# SH1_-_CAN.net
KiCad netlist of a schematic drawn in Altium Designer
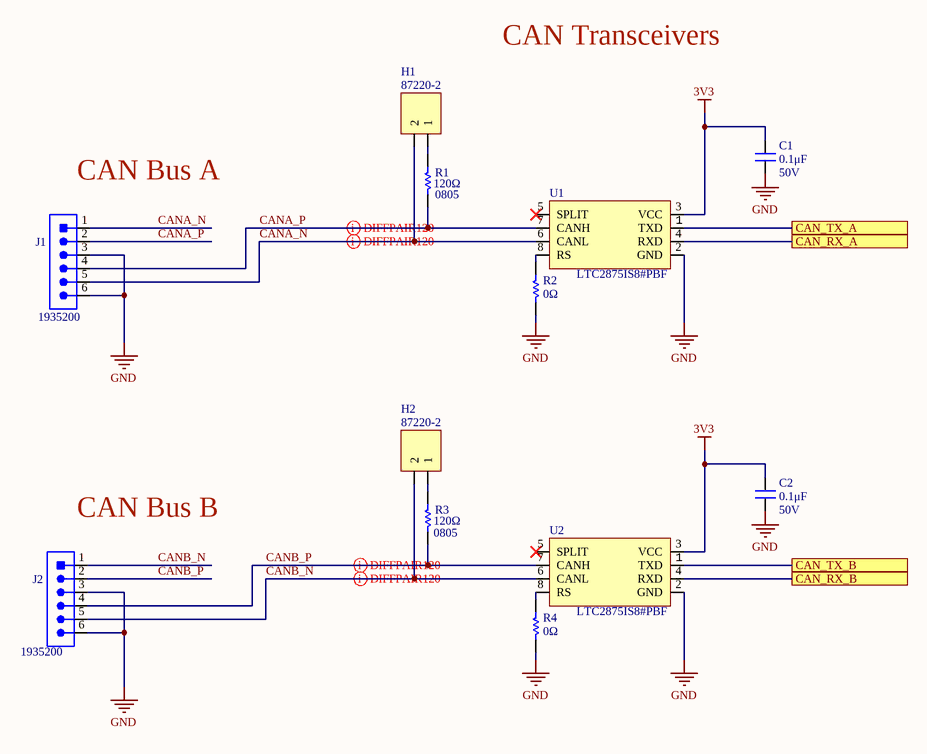
[diagram p0: SH1 - CAN.SchDoc]

(export (version "E")
  (design (tool "Eeschema 10.0.6"))
  (components
    (comp (ref "C1")
      (value "0.1μF")
      (footprint "CAP2012")
      (description "CAP CER 0.1UF 50V X7R 0805")
      (fields
        (field (name "VOLTAGE RATING") "50V")
        (field (name "LCSC PART #") "C49678")
        (field (name "Comment") "CAP_0.1uF_50V_0805")
      )
      (libsource (lib "UWRT_Schematic_Library_2020") (part "CAP_0.1uF_50V_0805"))
    )
    (comp (ref "C2")
      (value "0.1μF")
      (footprint "CAP2012")
      (description "CAP CER 0.1UF 50V X7R 0805")
      (fields
        (field (name "VOLTAGE RATING") "50V")
        (field (name "LCSC PART #") "C49678")
        (field (name "Comment") "CAP_0.1uF_50V_0805")
      )
      (libsource (lib "UWRT_Schematic_Library_2020") (part "CAP_0.1uF_50V_0805"))
    )
    (comp (ref "H1")
      (value "JUMPER")
      (footprint "HDR1X2")
      (description "HEADER 2X1")
      (fields (field (name "MANUFACTURER PART NUMBER 1") "87220-2"))
      (libsource (lib "UWRT_Schematic_Library_2020") (part "JUMPER"))
    )
    (comp (ref "H2")
      (value "JUMPER")
      (footprint "HDR1X2")
      (description "HEADER 2X1")
      (fields (field (name "MANUFACTURER PART NUMBER 1") "87220-2"))
      (libsource (lib "UWRT_Schematic_Library_2020") (part "JUMPER"))
    )
    (comp (ref "J1")
      (value "CON_6POS_SCREW_TERM")
      (footprint "1935200")
      (description "TERM BLK 6POS SIDE ENTRY 5MM")
      (fields (field (name "MANUFACTURER PART NUMBER 1") "1935200"))
      (libsource (lib "UWRT_Schematic_Library_2020") (part "CON_6POS_SCREW_TERM"))
    )
    (comp (ref "J2")
      (value "CON_6POS_SCREW_TERM")
      (footprint "1935200")
      (description "TERM BLK 6POS SIDE ENTRY 5MM")
      (fields (field (name "MANUFACTURER PART NUMBER 1") "1935200"))
      (libsource (lib "UWRT_Schematic_Library_2020") (part "CON_6POS_SCREW_TERM"))
    )
    (comp (ref "R1")
      (value "120Ω")
      (footprint "RESC0805")
      (description "RES 120 OHM 1% 1/8W 0805")
      (fields
        (field (name "LCSC PART #") "C17437")
        (field (name "PACKAGE/FOOTPRINT") "0805")
        (field (name "Comment") "RES_120Ω_0805_1%")
      )
      (libsource (lib "UWRT_Schematic_Library_2020") (part "RES_120Ω_0805_1%"))
    )
    (comp (ref "R2")
      (value "0Ω")
      (footprint "RESC0805")
      (description "RES 0 OHM JUMPER 1/8W 0805")
      (fields (field (name "LCSC PART #") "C17477") (field (name "Comment") "RES_0Ω_0805"))
      (libsource (lib "UWRT_Schematic_Library_2020") (part "RES_0Ω_0805"))
    )
    (comp (ref "R3")
      (value "120Ω")
      (footprint "RESC0805")
      (description "RES 120 OHM 1% 1/8W 0805")
      (fields
        (field (name "LCSC PART #") "C17437")
        (field (name "PACKAGE/FOOTPRINT") "0805")
        (field (name "Comment") "RES_120Ω_0805_1%")
      )
      (libsource (lib "UWRT_Schematic_Library_2020") (part "RES_120Ω_0805_1%"))
    )
    (comp (ref "R4")
      (value "0Ω")
      (footprint "RESC0805")
      (description "RES 0 OHM JUMPER 1/8W 0805")
      (fields (field (name "LCSC PART #") "C17477") (field (name "Comment") "RES_0Ω_0805"))
      (libsource (lib "UWRT_Schematic_Library_2020") (part "RES_0Ω_0805"))
    )
    (comp (ref "U1")
      (value "IC_CAN_TRANSCEIVER")
      (footprint "LT-S8_N")
      (description "IC TXRX CAN 4MBPS 8SO")
      (fields
        (field (name "MANUFACTURER PART NUMBER 1") "LTC2875IS8#PBF")
        (field (name "LCSC PART #") "C117076")
      )
      (libsource (lib "UWRT_Schematic_Library_2020") (part "IC_CAN_TRANSCEIVER"))
    )
    (comp (ref "U2")
      (value "IC_CAN_TRANSCEIVER")
      (footprint "LT-S8_N")
      (description "IC TXRX CAN 4MBPS 8SO")
      (fields
        (field (name "MANUFACTURER PART NUMBER 1") "LTC2875IS8#PBF")
        (field (name "LCSC PART #") "C117076")
      )
      (libsource (lib "UWRT_Schematic_Library_2020") (part "IC_CAN_TRANSCEIVER"))
    )
  )
  (nets
    (net (code "1") (name "/CANA_N") (class "Default")
      (node (ref "H1") (pin "2") (pinfunction "2_2") (pintype "passive"))
      (node (ref "J1") (pin "1") (pinfunction "1_1") (pintype "passive"))
      (node (ref "J1") (pin "5") (pinfunction "5_5") (pintype "passive"))
      (node (ref "U1") (pin "6") (pinfunction "CANL_6") (pintype "passive"))
    )
    (net (code "2") (name "/CANA_P") (class "Default")
      (node (ref "J1") (pin "2") (pinfunction "2_2") (pintype "passive"))
      (node (ref "J1") (pin "4") (pinfunction "4_4") (pintype "passive"))
      (node (ref "R1") (pin "1") (pinfunction "1_1") (pintype "passive"))
      (node (ref "U1") (pin "7") (pinfunction "CANH_7") (pintype "passive"))
    )
    (net (code "3") (name "/CANB_N") (class "Default")
      (node (ref "H2") (pin "2") (pinfunction "2_2") (pintype "passive"))
      (node (ref "J2") (pin "1") (pinfunction "1_1") (pintype "passive"))
      (node (ref "J2") (pin "5") (pinfunction "5_5") (pintype "passive"))
      (node (ref "U2") (pin "6") (pinfunction "CANL_6") (pintype "passive"))
    )
    (net (code "4") (name "/CANB_P") (class "Default")
      (node (ref "J2") (pin "2") (pinfunction "2_2") (pintype "passive"))
      (node (ref "J2") (pin "4") (pinfunction "4_4") (pintype "passive"))
      (node (ref "R3") (pin "1") (pinfunction "1_1") (pintype "passive"))
      (node (ref "U2") (pin "7") (pinfunction "CANH_7") (pintype "passive"))
    )
    (net (code "5") (name "/CAN_RX_A") (class "Default")
      (node (ref "U1") (pin "4") (pinfunction "RXD_4") (pintype "passive"))
    )
    (net (code "6") (name "/CAN_RX_B") (class "Default")
      (node (ref "U2") (pin "4") (pinfunction "RXD_4") (pintype "passive"))
    )
    (net (code "7") (name "/CAN_TX_A") (class "Default")
      (node (ref "U1") (pin "1") (pinfunction "TXD_1") (pintype "passive"))
    )
    (net (code "8") (name "/CAN_TX_B") (class "Default")
      (node (ref "U2") (pin "1") (pinfunction "TXD_1") (pintype "passive"))
    )
    (net (code "9") (name "3V3") (class "Default")
      (node (ref "C1") (pin "1") (pinfunction "1_1") (pintype "passive"))
      (node (ref "C2") (pin "1") (pinfunction "1_1") (pintype "passive"))
      (node (ref "U1") (pin "3") (pinfunction "VCC_3") (pintype "passive"))
      (node (ref "U2") (pin "3") (pinfunction "VCC_3") (pintype "passive"))
    )
    (net (code "10") (name "GND") (class "Default")
      (node (ref "C1") (pin "2") (pinfunction "2_2") (pintype "passive"))
      (node (ref "C2") (pin "2") (pinfunction "2_2") (pintype "passive"))
      (node (ref "J1") (pin "3") (pinfunction "3_3") (pintype "passive"))
      (node (ref "J1") (pin "6") (pinfunction "6_6") (pintype "passive"))
      (node (ref "J2") (pin "3") (pinfunction "3_3") (pintype "passive"))
      (node (ref "J2") (pin "6") (pinfunction "6_6") (pintype "passive"))
      (node (ref "R2") (pin "1") (pinfunction "1_1") (pintype "passive"))
      (node (ref "R4") (pin "1") (pinfunction "1_1") (pintype "passive"))
      (node (ref "U1") (pin "2") (pinfunction "GND_2") (pintype "passive"))
      (node (ref "U2") (pin "2") (pinfunction "GND_2") (pintype "passive"))
    )
    (net (code "11") (name "Net-(H1-Pad1)") (class "Default")
      (node (ref "H1") (pin "1") (pinfunction "1_1") (pintype "passive"))
      (node (ref "R1") (pin "2") (pinfunction "2_2") (pintype "passive"))
    )
    (net (code "12") (name "Net-(H2-Pad1)") (class "Default")
      (node (ref "H2") (pin "1") (pinfunction "1_1") (pintype "passive"))
      (node (ref "R3") (pin "2") (pinfunction "2_2") (pintype "passive"))
    )
    (net (code "13") (name "Net-(U1-RS)") (class "Default")
      (node (ref "R2") (pin "2") (pinfunction "2_2") (pintype "passive"))
      (node (ref "U1") (pin "8") (pinfunction "RS_8") (pintype "passive"))
    )
    (net (code "14") (name "Net-(U2-RS)") (class "Default")
      (node (ref "R4") (pin "2") (pinfunction "2_2") (pintype "passive"))
      (node (ref "U2") (pin "8") (pinfunction "RS_8") (pintype "passive"))
    )
    (net (code "15") (name "unconnected-(U1-SPLIT-Pad5)") (class "Default")
      (node (ref "U1") (pin "5") (pinfunction "SPLIT_5") (pintype "passive+no_connect"))
    )
    (net (code "16") (name "unconnected-(U2-SPLIT-Pad5)") (class "Default")
      (node (ref "U2") (pin "5") (pinfunction "SPLIT_5") (pintype "passive+no_connect"))
    )
  )
)
